# IORJ45.net
KiCad netlist of a schematic drawn in EAGLE
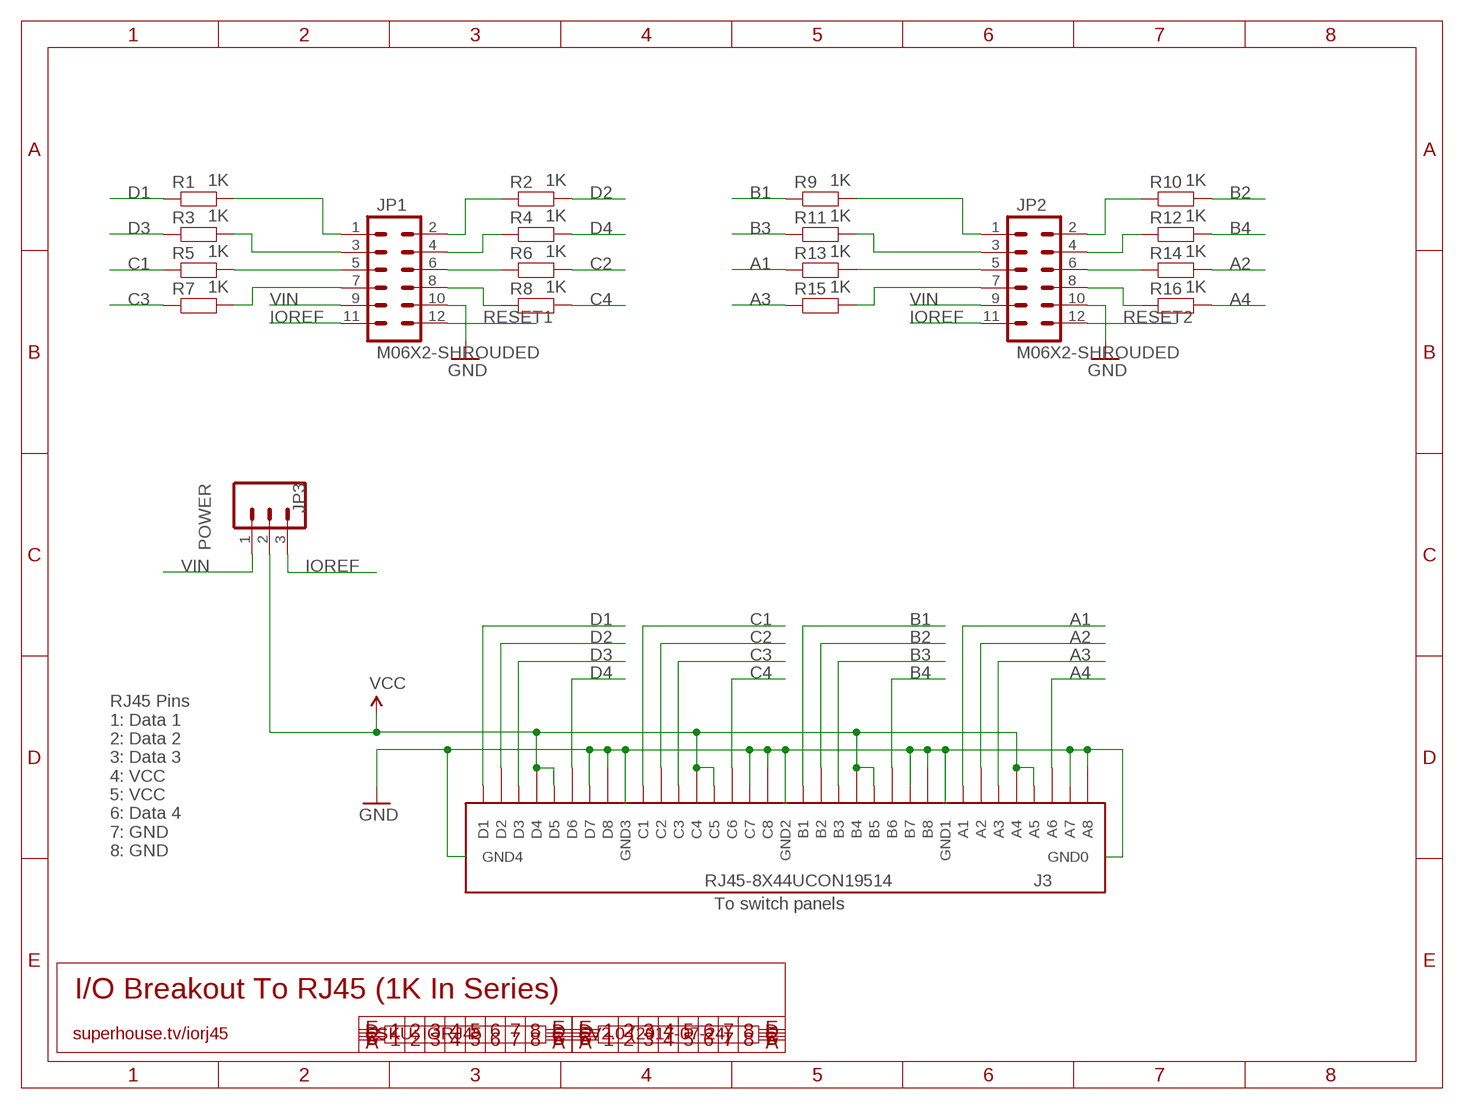
[diagram p0: schematic, sheet 1]

(export (version "E")
  (design (tool "Eeschema 10.0.6"))
  (components
    (comp (ref "J3")
      (value "RJ45-8X44UCON19514")
      (footprint "eagle-import:RJ45-8X4")
      (libsource (lib "eagle-import") (part "RJ45-8X44UCON19514"))
    )
    (comp (ref "JP1")
      (value "M06X2-SHROUDED")
      (footprint "eagle-import:2X6-SHROUDED")
      (libsource (lib "eagle-import") (part "M06X2-SHROUDED"))
    )
    (comp (ref "JP2")
      (value "M06X2-SHROUDED")
      (footprint "eagle-import:2X6-SHROUDED")
      (libsource (lib "eagle-import") (part "M06X2-SHROUDED"))
    )
    (comp (ref "JP3")
      (value "POWER")
      (footprint "eagle-import:1X03-P")
      (libsource (lib "eagle-import") (part "M03-PIN"))
    )
    (comp (ref "R1")
      (value "1K")
      (footprint "eagle-import:R0603")
      (libsource (lib "eagle-import") (part "RESISTOR0603"))
    )
    (comp (ref "R2")
      (value "1K")
      (footprint "eagle-import:R0603")
      (libsource (lib "eagle-import") (part "RESISTOR0603"))
    )
    (comp (ref "R3")
      (value "1K")
      (footprint "eagle-import:R0603")
      (libsource (lib "eagle-import") (part "RESISTOR0603"))
    )
    (comp (ref "R4")
      (value "1K")
      (footprint "eagle-import:R0603")
      (libsource (lib "eagle-import") (part "RESISTOR0603"))
    )
    (comp (ref "R5")
      (value "1K")
      (footprint "eagle-import:R0603")
      (libsource (lib "eagle-import") (part "RESISTOR0603"))
    )
    (comp (ref "R6")
      (value "1K")
      (footprint "eagle-import:R0603")
      (libsource (lib "eagle-import") (part "RESISTOR0603"))
    )
    (comp (ref "R7")
      (value "1K")
      (footprint "eagle-import:R0603")
      (libsource (lib "eagle-import") (part "RESISTOR0603"))
    )
    (comp (ref "R8")
      (value "1K")
      (footprint "eagle-import:R0603")
      (libsource (lib "eagle-import") (part "RESISTOR0603"))
    )
    (comp (ref "R9")
      (value "1K")
      (footprint "eagle-import:R0603")
      (libsource (lib "eagle-import") (part "RESISTOR0603"))
    )
    (comp (ref "R10")
      (value "1K")
      (footprint "eagle-import:R0603")
      (libsource (lib "eagle-import") (part "RESISTOR0603"))
    )
    (comp (ref "R11")
      (value "1K")
      (footprint "eagle-import:R0603")
      (libsource (lib "eagle-import") (part "RESISTOR0603"))
    )
    (comp (ref "R12")
      (value "1K")
      (footprint "eagle-import:R0603")
      (libsource (lib "eagle-import") (part "RESISTOR0603"))
    )
    (comp (ref "R13")
      (value "1K")
      (footprint "eagle-import:R0603")
      (libsource (lib "eagle-import") (part "RESISTOR0603"))
    )
    (comp (ref "R14")
      (value "1K")
      (footprint "eagle-import:R0603")
      (libsource (lib "eagle-import") (part "RESISTOR0603"))
    )
    (comp (ref "R15")
      (value "1K")
      (footprint "eagle-import:R0603")
      (libsource (lib "eagle-import") (part "RESISTOR0603"))
    )
    (comp (ref "R16")
      (value "1K")
      (footprint "eagle-import:R0603")
      (libsource (lib "eagle-import") (part "RESISTOR0603"))
    )
  )
  (nets
    (net (code "1") (name "/A1") (class "Default")
      (node (ref "J3") (pin "A1") (pinfunction "A1_A1") (pintype "bidirectional"))
      (node (ref "R13") (pin "1") (pinfunction "1_1") (pintype "passive"))
    )
    (net (code "2") (name "/A2") (class "Default")
      (node (ref "J3") (pin "A2") (pinfunction "A2_A2") (pintype "bidirectional"))
      (node (ref "R14") (pin "2") (pinfunction "2_2") (pintype "passive"))
    )
    (net (code "3") (name "/A3") (class "Default")
      (node (ref "J3") (pin "A3") (pinfunction "A3_A3") (pintype "bidirectional"))
      (node (ref "R15") (pin "1") (pinfunction "1_1") (pintype "passive"))
    )
    (net (code "4") (name "/A4") (class "Default")
      (node (ref "J3") (pin "A6") (pinfunction "A6_A6") (pintype "bidirectional"))
      (node (ref "R16") (pin "2") (pinfunction "2_2") (pintype "passive"))
    )
    (net (code "5") (name "/B1") (class "Default")
      (node (ref "J3") (pin "B1") (pinfunction "B1_B1") (pintype "bidirectional"))
      (node (ref "R9") (pin "1") (pinfunction "1_1") (pintype "passive"))
    )
    (net (code "6") (name "/B2") (class "Default")
      (node (ref "J3") (pin "B2") (pinfunction "B2_B2") (pintype "bidirectional"))
      (node (ref "R10") (pin "2") (pinfunction "2_2") (pintype "passive"))
    )
    (net (code "7") (name "/B3") (class "Default")
      (node (ref "J3") (pin "B3") (pinfunction "B3_B3") (pintype "bidirectional"))
      (node (ref "R11") (pin "1") (pinfunction "1_1") (pintype "passive"))
    )
    (net (code "8") (name "/B4") (class "Default")
      (node (ref "J3") (pin "B6") (pinfunction "B6_B6") (pintype "bidirectional"))
      (node (ref "R12") (pin "2") (pinfunction "2_2") (pintype "passive"))
    )
    (net (code "9") (name "/C1") (class "Default")
      (node (ref "J3") (pin "C1") (pinfunction "C1_C1") (pintype "bidirectional"))
      (node (ref "R5") (pin "1") (pinfunction "1_1") (pintype "passive"))
    )
    (net (code "10") (name "/C2") (class "Default")
      (node (ref "J3") (pin "C2") (pinfunction "C2_C2") (pintype "bidirectional"))
      (node (ref "R6") (pin "2") (pinfunction "2_2") (pintype "passive"))
    )
    (net (code "11") (name "/C3") (class "Default")
      (node (ref "J3") (pin "C3") (pinfunction "C3_C3") (pintype "bidirectional"))
      (node (ref "R7") (pin "1") (pinfunction "1_1") (pintype "passive"))
    )
    (net (code "12") (name "/C4") (class "Default")
      (node (ref "J3") (pin "C6") (pinfunction "C6_C6") (pintype "bidirectional"))
      (node (ref "R8") (pin "2") (pinfunction "2_2") (pintype "passive"))
    )
    (net (code "13") (name "/D1") (class "Default")
      (node (ref "J3") (pin "D1") (pinfunction "D1_D1") (pintype "bidirectional"))
      (node (ref "R1") (pin "1") (pinfunction "1_1") (pintype "passive"))
    )
    (net (code "14") (name "/D2") (class "Default")
      (node (ref "J3") (pin "D2") (pinfunction "D2_D2") (pintype "bidirectional"))
      (node (ref "R2") (pin "2") (pinfunction "2_2") (pintype "passive"))
    )
    (net (code "15") (name "/D3") (class "Default")
      (node (ref "J3") (pin "D3") (pinfunction "D3_D3") (pintype "bidirectional"))
      (node (ref "R3") (pin "1") (pinfunction "1_1") (pintype "passive"))
    )
    (net (code "16") (name "/D4") (class "Default")
      (node (ref "J3") (pin "D6") (pinfunction "D6_D6") (pintype "bidirectional"))
      (node (ref "R4") (pin "2") (pinfunction "2_2") (pintype "passive"))
    )
    (net (code "17") (name "/IOREF") (class "Default")
      (node (ref "JP1") (pin "11") (pinfunction "11_11") (pintype "passive"))
      (node (ref "JP2") (pin "11") (pinfunction "11_11") (pintype "passive"))
      (node (ref "JP3") (pin "3") (pinfunction "3_3") (pintype "passive"))
    )
    (net (code "18") (name "/RESET1") (class "Default")
      (node (ref "JP1") (pin "12") (pinfunction "12_12") (pintype "passive"))
    )
    (net (code "19") (name "/RESET2") (class "Default")
      (node (ref "JP2") (pin "12") (pinfunction "12_12") (pintype "passive"))
    )
    (net (code "20") (name "/VIN") (class "Default")
      (node (ref "JP1") (pin "9") (pinfunction "9_9") (pintype "passive"))
      (node (ref "JP2") (pin "9") (pinfunction "9_9") (pintype "passive"))
      (node (ref "JP3") (pin "1") (pinfunction "1_1") (pintype "passive"))
    )
    (net (code "21") (name "GND") (class "Default")
      (node (ref "J3") (pin "A7") (pinfunction "A7_A7") (pintype "bidirectional"))
      (node (ref "J3") (pin "A8") (pinfunction "A8_A8") (pintype "bidirectional"))
      (node (ref "J3") (pin "B7") (pinfunction "B7_B7") (pintype "bidirectional"))
      (node (ref "J3") (pin "B8") (pinfunction "B8_B8") (pintype "bidirectional"))
      (node (ref "J3") (pin "C7") (pinfunction "C7_C7") (pintype "bidirectional"))
      (node (ref "J3") (pin "C8") (pinfunction "C8_C8") (pintype "bidirectional"))
      (node (ref "J3") (pin "D7") (pinfunction "D7_D7") (pintype "bidirectional"))
      (node (ref "J3") (pin "D8") (pinfunction "D8_D8") (pintype "bidirectional"))
      (node (ref "J3") (pin "GND0") (pinfunction "GND0_GND0") (pintype "power_in"))
      (node (ref "J3") (pin "GND1") (pinfunction "GND1_GND1") (pintype "power_in"))
      (node (ref "J3") (pin "GND2") (pinfunction "GND2_GND2") (pintype "power_in"))
      (node (ref "J3") (pin "GND3") (pinfunction "GND3_GND3") (pintype "power_in"))
      (node (ref "J3") (pin "GND4") (pinfunction "GND4_GND4") (pintype "power_in"))
      (node (ref "JP1") (pin "10") (pinfunction "10_10") (pintype "passive"))
      (node (ref "JP2") (pin "10") (pinfunction "10_10") (pintype "passive"))
    )
    (net (code "22") (name "Net-(JP1-Pad1)") (class "Default")
      (node (ref "JP1") (pin "1") (pinfunction "1_1") (pintype "passive"))
      (node (ref "R1") (pin "2") (pinfunction "2_2") (pintype "passive"))
    )
    (net (code "23") (name "Net-(JP1-Pad2)") (class "Default")
      (node (ref "JP1") (pin "2") (pinfunction "2_2") (pintype "passive"))
      (node (ref "R2") (pin "1") (pinfunction "1_1") (pintype "passive"))
    )
    (net (code "24") (name "Net-(JP1-Pad3)") (class "Default")
      (node (ref "JP1") (pin "3") (pinfunction "3_3") (pintype "passive"))
      (node (ref "R3") (pin "2") (pinfunction "2_2") (pintype "passive"))
    )
    (net (code "25") (name "Net-(JP1-Pad4)") (class "Default")
      (node (ref "JP1") (pin "4") (pinfunction "4_4") (pintype "passive"))
      (node (ref "R4") (pin "1") (pinfunction "1_1") (pintype "passive"))
    )
    (net (code "26") (name "Net-(JP1-Pad5)") (class "Default")
      (node (ref "JP1") (pin "5") (pinfunction "5_5") (pintype "passive"))
      (node (ref "R5") (pin "2") (pinfunction "2_2") (pintype "passive"))
    )
    (net (code "27") (name "Net-(JP1-Pad6)") (class "Default")
      (node (ref "JP1") (pin "6") (pinfunction "6_6") (pintype "passive"))
      (node (ref "R6") (pin "1") (pinfunction "1_1") (pintype "passive"))
    )
    (net (code "28") (name "Net-(JP1-Pad7)") (class "Default")
      (node (ref "JP1") (pin "7") (pinfunction "7_7") (pintype "passive"))
      (node (ref "R7") (pin "2") (pinfunction "2_2") (pintype "passive"))
    )
    (net (code "29") (name "Net-(JP1-Pad8)") (class "Default")
      (node (ref "JP1") (pin "8") (pinfunction "8_8") (pintype "passive"))
      (node (ref "R8") (pin "1") (pinfunction "1_1") (pintype "passive"))
    )
    (net (code "30") (name "Net-(JP2-Pad1)") (class "Default")
      (node (ref "JP2") (pin "1") (pinfunction "1_1") (pintype "passive"))
      (node (ref "R9") (pin "2") (pinfunction "2_2") (pintype "passive"))
    )
    (net (code "31") (name "Net-(JP2-Pad2)") (class "Default")
      (node (ref "JP2") (pin "2") (pinfunction "2_2") (pintype "passive"))
      (node (ref "R10") (pin "1") (pinfunction "1_1") (pintype "passive"))
    )
    (net (code "32") (name "Net-(JP2-Pad3)") (class "Default")
      (node (ref "JP2") (pin "3") (pinfunction "3_3") (pintype "passive"))
      (node (ref "R11") (pin "2") (pinfunction "2_2") (pintype "passive"))
    )
    (net (code "33") (name "Net-(JP2-Pad4)") (class "Default")
      (node (ref "JP2") (pin "4") (pinfunction "4_4") (pintype "passive"))
      (node (ref "R12") (pin "1") (pinfunction "1_1") (pintype "passive"))
    )
    (net (code "34") (name "Net-(JP2-Pad5)") (class "Default")
      (node (ref "JP2") (pin "5") (pinfunction "5_5") (pintype "passive"))
      (node (ref "R13") (pin "2") (pinfunction "2_2") (pintype "passive"))
    )
    (net (code "35") (name "Net-(JP2-Pad6)") (class "Default")
      (node (ref "JP2") (pin "6") (pinfunction "6_6") (pintype "passive"))
      (node (ref "R14") (pin "1") (pinfunction "1_1") (pintype "passive"))
    )
    (net (code "36") (name "Net-(JP2-Pad7)") (class "Default")
      (node (ref "JP2") (pin "7") (pinfunction "7_7") (pintype "passive"))
      (node (ref "R15") (pin "2") (pinfunction "2_2") (pintype "passive"))
    )
    (net (code "37") (name "Net-(JP2-Pad8)") (class "Default")
      (node (ref "JP2") (pin "8") (pinfunction "8_8") (pintype "passive"))
      (node (ref "R16") (pin "1") (pinfunction "1_1") (pintype "passive"))
    )
    (net (code "38") (name "VCC") (class "Default")
      (node (ref "J3") (pin "A4") (pinfunction "A4_A4") (pintype "bidirectional"))
      (node (ref "J3") (pin "A5") (pinfunction "A5_A5") (pintype "bidirectional"))
      (node (ref "J3") (pin "B4") (pinfunction "B4_B4") (pintype "bidirectional"))
      (node (ref "J3") (pin "B5") (pinfunction "B5_B5") (pintype "bidirectional"))
      (node (ref "J3") (pin "C4") (pinfunction "C4_C4") (pintype "bidirectional"))
      (node (ref "J3") (pin "C5") (pinfunction "C5_C5") (pintype "bidirectional"))
      (node (ref "J3") (pin "D4") (pinfunction "D4_D4") (pintype "bidirectional"))
      (node (ref "J3") (pin "D5") (pinfunction "D5_D5") (pintype "bidirectional"))
      (node (ref "JP3") (pin "2") (pinfunction "2_2") (pintype "passive"))
    )
  )
)
